# Status_Light_Control.net
KiCad netlist of a schematic drawn in Altium Designer
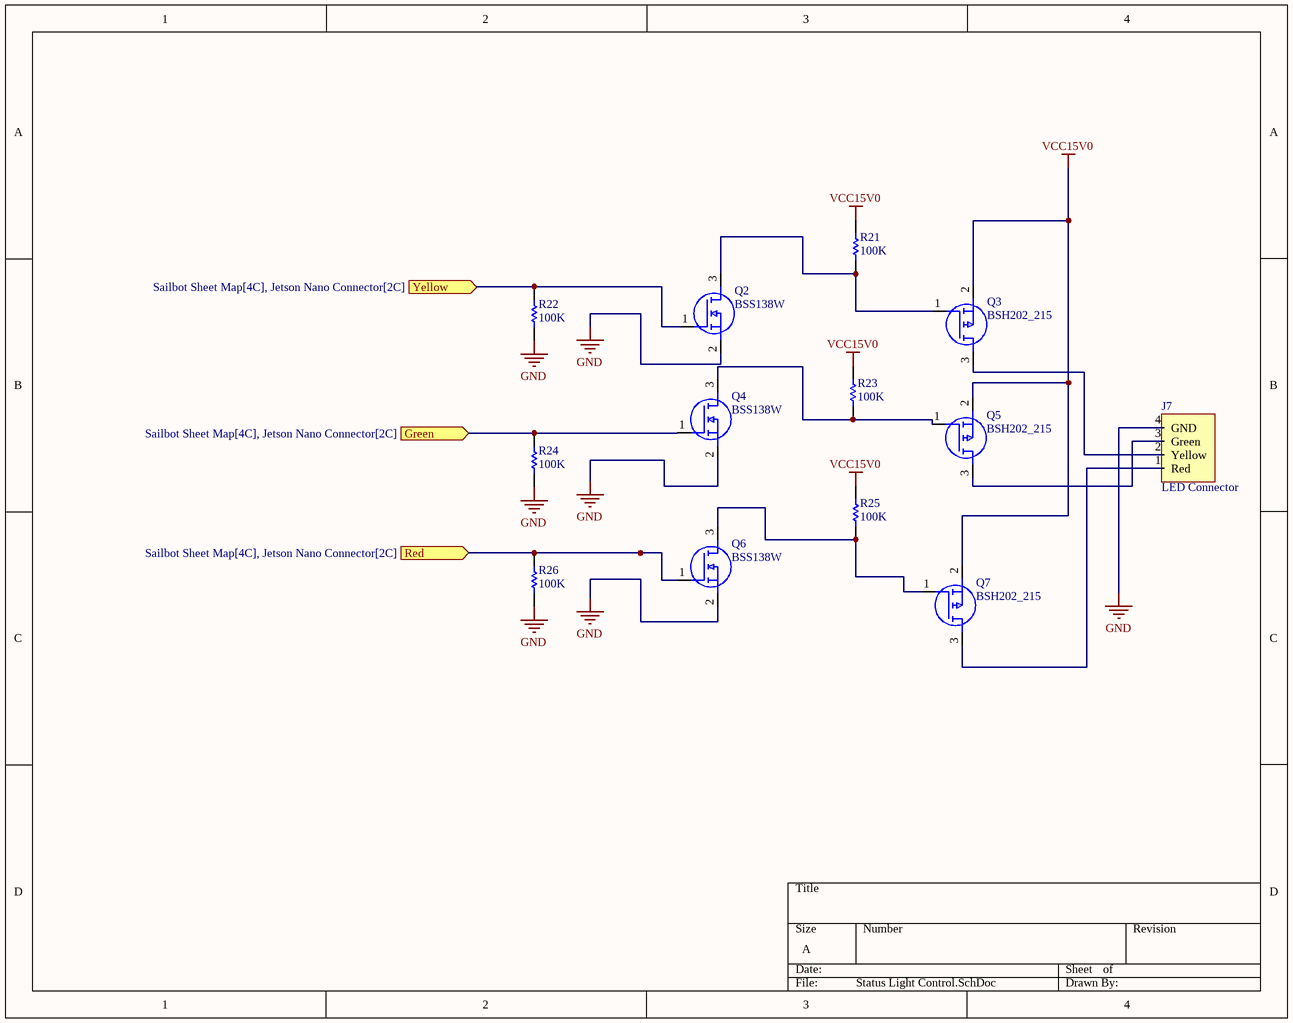
[diagram p0: Status Light Control.SchDoc]

(export (version "E")
  (design (tool "Eeschema 10.0.6"))
  (components
    (comp (ref "J7")
      (value "LED Connector")
      (footprint "4 Pin 0.1in Header")
      (libsource (lib "Sailbot Library") (part "LED Connector"))
    )
    (comp (ref "Q2")
      (value "BSS138W")
      (footprint "SOT65P210X110-3N")
      (description "BSS138W N-Channel MOSFET, 210 mA, 50 V, 3-Pin SOT-323 ON Semiconductor")
      (fields (field (name "MOUSER PART NUMBER") "512-BSS138W"))
      (libsource (lib "BSS138W") (part "BSS138W"))
    )
    (comp (ref "Q3")
      (value "BSH202_215")
      (footprint "SOT95P230X110-3N")
      (description "NEXPERIA - BSH202,215 - Power MOSFET, P Channel, 30 V, 520 mA, 0.63 ohm, SOT-23, Surface Mount")
      (fields
        (field (name "MOUSER PART NUMBER") "771-BSH202215")
        (field (name "MANUFACTURER_PART_NUMBER") "BSH202,215")
      )
      (libsource (lib "BSH202_215") (part "BSH202_215"))
    )
    (comp (ref "Q4")
      (value "BSS138W")
      (footprint "SOT65P210X110-3N")
      (description "BSS138W N-Channel MOSFET, 210 mA, 50 V, 3-Pin SOT-323 ON Semiconductor")
      (fields (field (name "MOUSER PART NUMBER") "512-BSS138W"))
      (libsource (lib "BSS138W") (part "BSS138W"))
    )
    (comp (ref "Q5")
      (value "BSH202_215")
      (footprint "SOT95P230X110-3N")
      (description "NEXPERIA - BSH202,215 - Power MOSFET, P Channel, 30 V, 520 mA, 0.63 ohm, SOT-23, Surface Mount")
      (fields
        (field (name "MOUSER PART NUMBER") "771-BSH202215")
        (field (name "MANUFACTURER_PART_NUMBER") "BSH202,215")
      )
      (libsource (lib "BSH202_215") (part "BSH202_215"))
    )
    (comp (ref "Q6")
      (value "BSS138W")
      (footprint "SOT65P210X110-3N")
      (description "BSS138W N-Channel MOSFET, 210 mA, 50 V, 3-Pin SOT-323 ON Semiconductor")
      (fields (field (name "MOUSER PART NUMBER") "512-BSS138W"))
      (libsource (lib "BSS138W") (part "BSS138W"))
    )
    (comp (ref "Q7")
      (value "BSH202_215")
      (footprint "SOT95P230X110-3N")
      (description "NEXPERIA - BSH202,215 - Power MOSFET, P Channel, 30 V, 520 mA, 0.63 ohm, SOT-23, Surface Mount")
      (fields
        (field (name "MOUSER PART NUMBER") "771-BSH202215")
        (field (name "MANUFACTURER_PART_NUMBER") "BSH202,215")
      )
      (libsource (lib "BSH202_215") (part "BSH202_215"))
    )
    (comp (ref "R21")
      (value "100K")
      (footprint "6-0805_M")
      (description "Resistor")
      (libsource (lib "Simulation Generic Components") (part "Resistor"))
    )
    (comp (ref "R22")
      (value "100K")
      (footprint "6-0805_M")
      (description "Resistor")
      (libsource (lib "Simulation Generic Components") (part "Resistor"))
    )
    (comp (ref "R23")
      (value "100K")
      (footprint "6-0805_M")
      (description "Resistor")
      (libsource (lib "Simulation Generic Components") (part "Resistor"))
    )
    (comp (ref "R24")
      (value "100K")
      (footprint "6-0805_M")
      (description "Resistor")
      (libsource (lib "Simulation Generic Components") (part "Resistor"))
    )
    (comp (ref "R25")
      (value "100K")
      (footprint "6-0805_M")
      (description "Resistor")
      (libsource (lib "Simulation Generic Components") (part "Resistor"))
    )
    (comp (ref "R26")
      (value "100K")
      (footprint "6-0805_M")
      (description "Resistor")
      (libsource (lib "Simulation Generic Components") (part "Resistor"))
    )
  )
  (nets
    (net (code "1") (name "/Green") (class "Default")
      (node (ref "Q4") (pin "1") (pinfunction "G_1") (pintype "passive"))
      (node (ref "R24") (pin "2") (pinfunction "2_2") (pintype "passive"))
    )
    (net (code "2") (name "/Red") (class "Default")
      (node (ref "Q6") (pin "1") (pinfunction "G_1") (pintype "passive"))
      (node (ref "R26") (pin "2") (pinfunction "2_2") (pintype "passive"))
    )
    (net (code "3") (name "/Yellow") (class "Default")
      (node (ref "Q2") (pin "1") (pinfunction "G_1") (pintype "passive"))
      (node (ref "R22") (pin "2") (pinfunction "2_2") (pintype "passive"))
    )
    (net (code "4") (name "GND") (class "Default")
      (node (ref "J7") (pin "4") (pinfunction "GND_4") (pintype "passive"))
      (node (ref "Q2") (pin "2") (pinfunction "S_2") (pintype "passive"))
      (node (ref "Q4") (pin "2") (pinfunction "S_2") (pintype "passive"))
      (node (ref "Q6") (pin "2") (pinfunction "S_2") (pintype "passive"))
      (node (ref "R22") (pin "1") (pinfunction "1_1") (pintype "passive"))
      (node (ref "R24") (pin "1") (pinfunction "1_1") (pintype "passive"))
      (node (ref "R26") (pin "1") (pinfunction "1_1") (pintype "passive"))
    )
    (net (code "5") (name "Net-(J7-Green)") (class "Default")
      (node (ref "J7") (pin "3") (pinfunction "Green_3") (pintype "passive"))
      (node (ref "Q5") (pin "3") (pinfunction "D_3") (pintype "passive"))
    )
    (net (code "6") (name "Net-(J7-Red)") (class "Default")
      (node (ref "J7") (pin "1") (pinfunction "Red_1") (pintype "passive"))
      (node (ref "Q7") (pin "3") (pinfunction "D_3") (pintype "passive"))
    )
    (net (code "7") (name "Net-(J7-Yellow)") (class "Default")
      (node (ref "J7") (pin "2") (pinfunction "Yellow_2") (pintype "passive"))
      (node (ref "Q3") (pin "3") (pinfunction "D_3") (pintype "passive"))
    )
    (net (code "8") (name "Net-(Q2-D)") (class "Default")
      (node (ref "Q2") (pin "3") (pinfunction "D_3") (pintype "passive"))
      (node (ref "Q3") (pin "1") (pinfunction "G_1") (pintype "passive"))
      (node (ref "R21") (pin "1") (pinfunction "1_1") (pintype "passive"))
    )
    (net (code "9") (name "Net-(Q4-D)") (class "Default")
      (node (ref "Q4") (pin "3") (pinfunction "D_3") (pintype "passive"))
      (node (ref "Q5") (pin "1") (pinfunction "G_1") (pintype "passive"))
      (node (ref "R23") (pin "1") (pinfunction "1_1") (pintype "passive"))
    )
    (net (code "10") (name "Net-(Q6-D)") (class "Default")
      (node (ref "Q6") (pin "3") (pinfunction "D_3") (pintype "passive"))
      (node (ref "Q7") (pin "1") (pinfunction "G_1") (pintype "passive"))
      (node (ref "R25") (pin "1") (pinfunction "1_1") (pintype "passive"))
    )
    (net (code "11") (name "VCC15V0") (class "Default")
      (node (ref "Q3") (pin "2") (pinfunction "S_2") (pintype "passive"))
      (node (ref "Q5") (pin "2") (pinfunction "S_2") (pintype "passive"))
      (node (ref "Q7") (pin "2") (pinfunction "S_2") (pintype "passive"))
      (node (ref "R21") (pin "2") (pinfunction "2_2") (pintype "passive"))
      (node (ref "R23") (pin "2") (pinfunction "2_2") (pintype "passive"))
      (node (ref "R25") (pin "2") (pinfunction "2_2") (pintype "passive"))
    )
  )
)
